# schematic_1.net
KiCad netlist of a schematic drawn in EAGLE
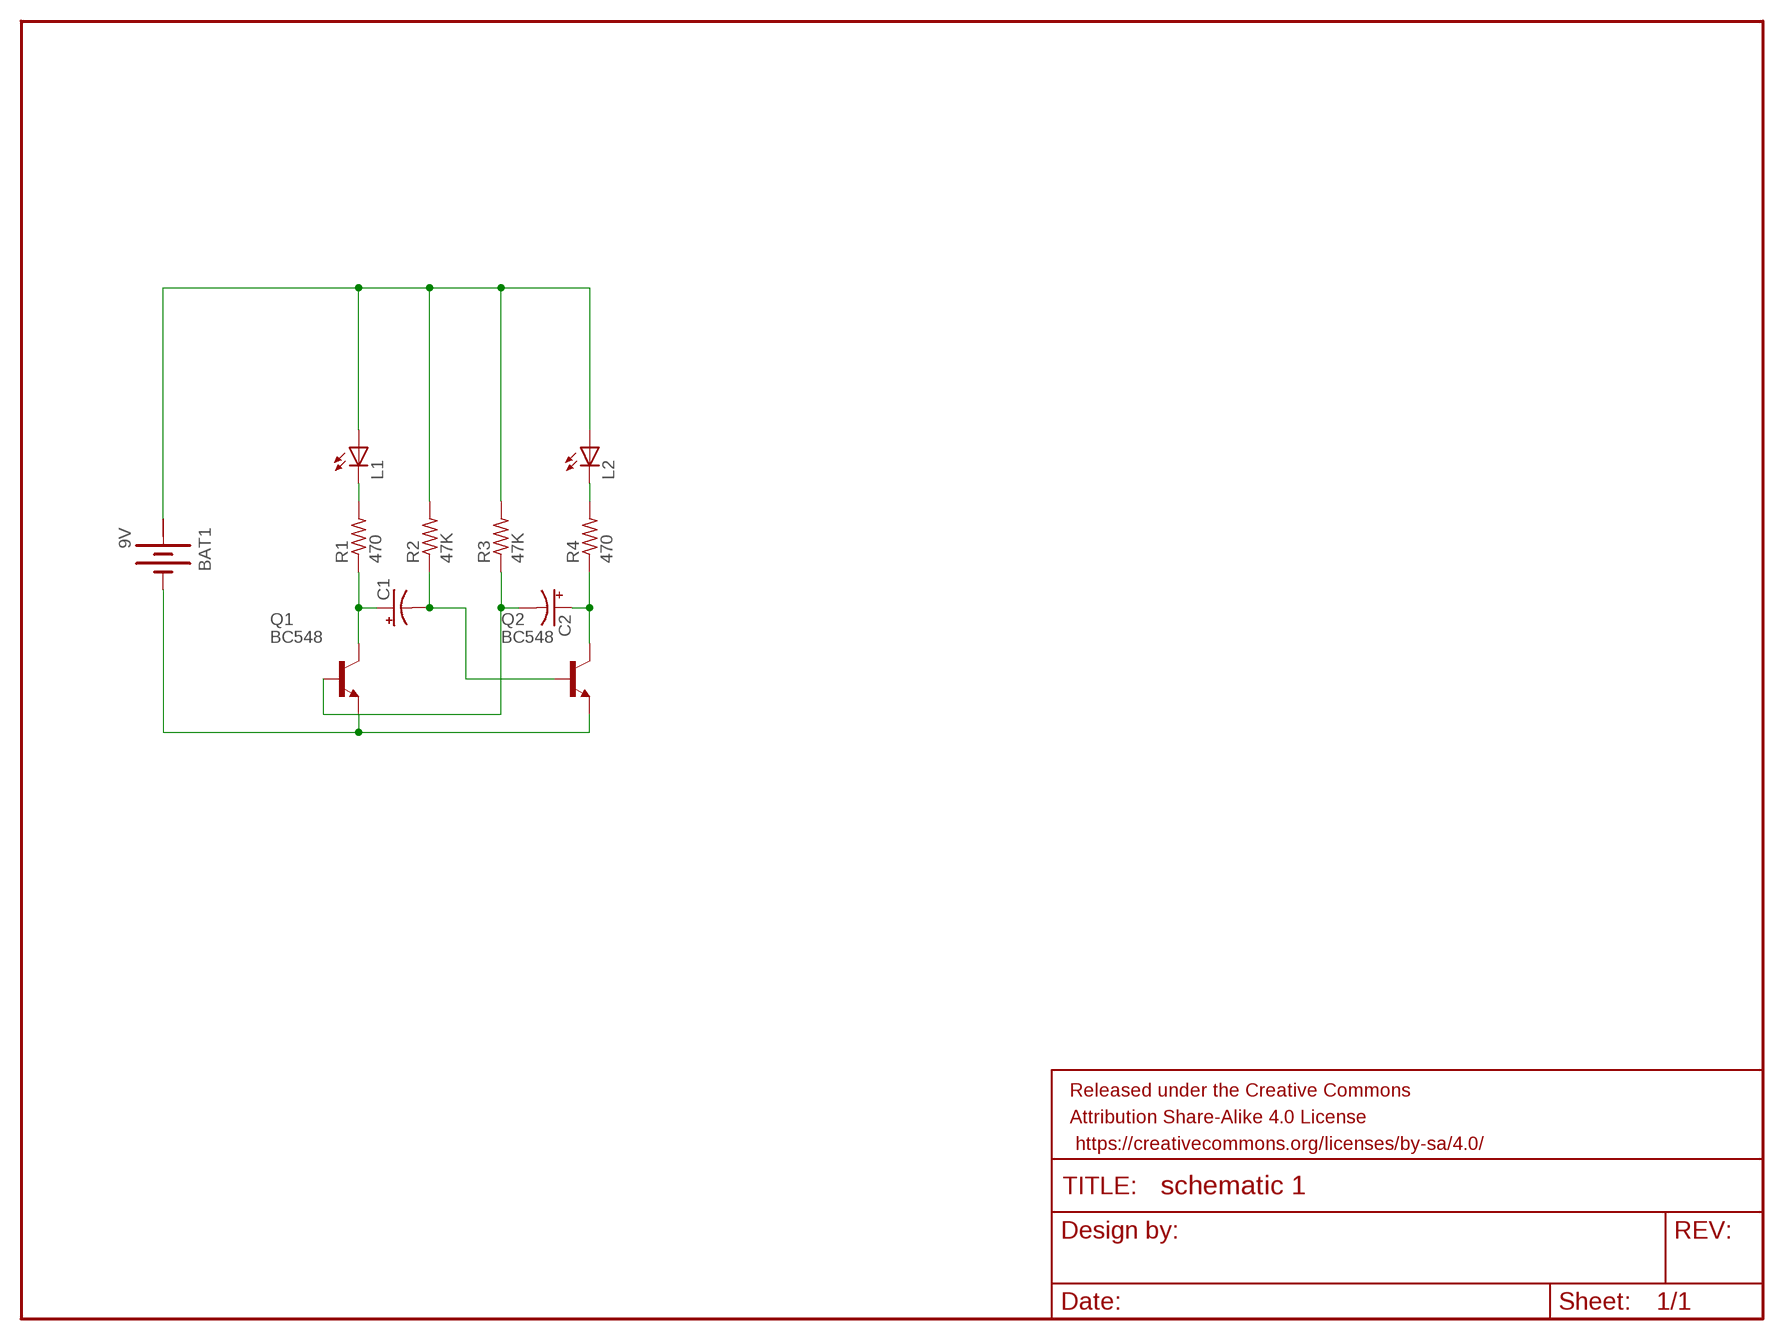
[diagram p0: schematic, sheet 1]

(export (version "E")
  (design (tool "Eeschema 10.0.6"))
  (components
    (comp (ref "BAT1")
      (value "9V")
      (footprint "eagle-import:BATTERY")
      (libsource (lib "eagle-import") (part "BATTERY"))
    )
    (comp (ref "C1")
      (value "CPOL-USE10-35")
      (footprint "eagle-import:EB35D")
      (libsource (lib "eagle-import") (part "CPOL-USE10-35"))
    )
    (comp (ref "C2")
      (value "CPOL-USE10-35")
      (footprint "eagle-import:EB35D")
      (libsource (lib "eagle-import") (part "CPOL-USE10-35"))
    )
    (comp (ref "FRAME1")
      (value "FRAME-LETTER")
      (footprint "eagle-import:CREATIVE_COMMONS")
      (libsource (lib "eagle-import") (part "FRAME-LETTER"))
    )
    (comp (ref "L1")
      (value "LEDLZR181")
      (footprint "eagle-import:LZR181")
      (libsource (lib "eagle-import") (part "LEDLZR181"))
    )
    (comp (ref "L2")
      (value "LEDLZR181")
      (footprint "eagle-import:LZR181")
      (libsource (lib "eagle-import") (part "LEDLZR181"))
    )
    (comp (ref "Q1")
      (value "BC548")
      (footprint "eagle-import:TO92-EBC")
      (libsource (lib "eagle-import") (part "BC548"))
    )
    (comp (ref "Q2")
      (value "BC548")
      (footprint "eagle-import:TO92-EBC")
      (libsource (lib "eagle-import") (part "BC548"))
    )
    (comp (ref "R1")
      (value "470")
      (footprint "eagle-import:M2012")
      (libsource (lib "eagle-import") (part "R-US_M2012"))
    )
    (comp (ref "R2")
      (value "47K")
      (footprint "eagle-import:M2012")
      (libsource (lib "eagle-import") (part "R-US_M2012"))
    )
    (comp (ref "R3")
      (value "47K")
      (footprint "eagle-import:M2012")
      (libsource (lib "eagle-import") (part "R-US_M2012"))
    )
    (comp (ref "R4")
      (value "470")
      (footprint "eagle-import:M2012")
      (libsource (lib "eagle-import") (part "R-US_M2012"))
    )
  )
  (nets
    (net (code "1") (name "/+") (class "Default")
      (node (ref "BAT1") (pin "+@1") (pinfunction "+_+@1") (pintype "power_in"))
    )
    (net (code "2") (name "Net-(BAT1-Pad+)") (class "Default")
      (node (ref "BAT1") (pin "+") (pinfunction "+_+") (pintype "power_in"))
      (node (ref "L1") (pin "A") (pinfunction "A_A") (pintype "passive"))
      (node (ref "L2") (pin "A") (pinfunction "A_A") (pintype "passive"))
      (node (ref "R2") (pin "2") (pinfunction "2_2") (pintype "passive"))
      (node (ref "R3") (pin "2") (pinfunction "2_2") (pintype "passive"))
    )
    (net (code "3") (name "Net-(BAT1-Pad-)") (class "Default")
      (node (ref "BAT1") (pin "-") (pinfunction "-_-") (pintype "power_in"))
      (node (ref "Q1") (pin "E") (pinfunction "E_E") (pintype "passive"))
      (node (ref "Q2") (pin "E") (pinfunction "E_E") (pintype "passive"))
    )
    (net (code "4") (name "Net-(C1-Pad+)") (class "Default")
      (node (ref "C1") (pin "+") (pinfunction "+_+") (pintype "passive"))
      (node (ref "Q1") (pin "C") (pinfunction "C_C") (pintype "passive"))
      (node (ref "R1") (pin "1") (pinfunction "1_1") (pintype "passive"))
    )
    (net (code "5") (name "Net-(C1-Pad-)") (class "Default")
      (node (ref "C1") (pin "-") (pinfunction "-_-") (pintype "passive"))
      (node (ref "Q2") (pin "B") (pinfunction "B_B") (pintype "passive"))
      (node (ref "R2") (pin "1") (pinfunction "1_1") (pintype "passive"))
    )
    (net (code "6") (name "Net-(C2-Pad+)") (class "Default")
      (node (ref "C2") (pin "+") (pinfunction "+_+") (pintype "passive"))
      (node (ref "Q2") (pin "C") (pinfunction "C_C") (pintype "passive"))
      (node (ref "R4") (pin "1") (pinfunction "1_1") (pintype "passive"))
    )
    (net (code "7") (name "Net-(C2-Pad-)") (class "Default")
      (node (ref "C2") (pin "-") (pinfunction "-_-") (pintype "passive"))
      (node (ref "Q1") (pin "B") (pinfunction "B_B") (pintype "passive"))
      (node (ref "R3") (pin "1") (pinfunction "1_1") (pintype "passive"))
    )
    (net (code "8") (name "Net-(L1-C)") (class "Default")
      (node (ref "L1") (pin "K") (pinfunction "C_K") (pintype "passive"))
      (node (ref "R1") (pin "2") (pinfunction "2_2") (pintype "passive"))
    )
    (net (code "9") (name "Net-(L2-C)") (class "Default")
      (node (ref "L2") (pin "K") (pinfunction "C_K") (pintype "passive"))
      (node (ref "R4") (pin "2") (pinfunction "2_2") (pintype "passive"))
    )
  )
)
